# node_captorIR.net
KiCad netlist of a schematic drawn in EAGLE
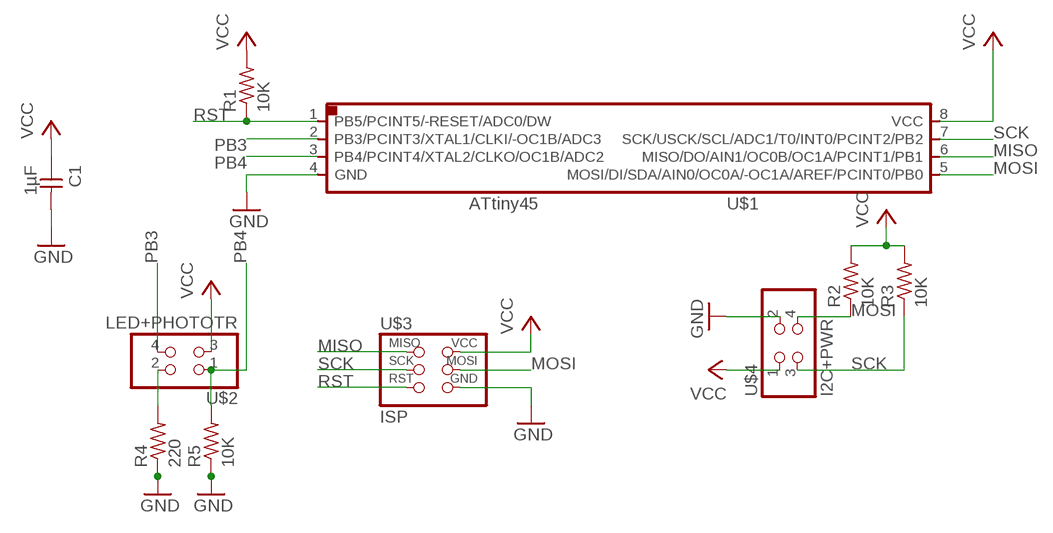
[diagram p0: schematic, sheet 1]

(export (version "E")
  (design (tool "Eeschema 10.0.6"))
  (components
    (comp (ref "C1")
      (value "1µF")
      (footprint "eagle-import:C1206FAB")
      (libsource (lib "eagle-import") (part "CAP-UNPOLARIZEDFAB"))
    )
    (comp (ref "R1")
      (value "10K")
      (footprint "eagle-import:R1206FAB")
      (libsource (lib "eagle-import") (part "RES-US1206FAB"))
    )
    (comp (ref "R2")
      (value "10K")
      (footprint "eagle-import:R1206FAB")
      (libsource (lib "eagle-import") (part "RES-US1206FAB"))
    )
    (comp (ref "R3")
      (value "10K")
      (footprint "eagle-import:R1206FAB")
      (libsource (lib "eagle-import") (part "RES-US1206FAB"))
    )
    (comp (ref "R4")
      (value "220")
      (footprint "eagle-import:R1206FAB")
      (libsource (lib "eagle-import") (part "RES-US1206FAB"))
    )
    (comp (ref "R5")
      (value "10K")
      (footprint "eagle-import:R1206FAB")
      (libsource (lib "eagle-import") (part "RES-US1206FAB"))
    )
    (comp (ref "U$1")
      (value "ATTINY45SI")
      (footprint "eagle-import:SOIC8")
      (libsource (lib "eagle-import") (part "ATTINY45SI"))
    )
    (comp (ref "U$2")
      (value "LED+PHOTOTR")
      (footprint "eagle-import:2X02SMD")
      (libsource (lib "eagle-import") (part "PINHD-2X2-SMD"))
    )
    (comp (ref "U$3")
      (value "ISP")
      (footprint "eagle-import:2X03SMD")
      (libsource (lib "eagle-import") (part "AVRISPSMD"))
    )
    (comp (ref "U$4")
      (value "I2C+PWR")
      (footprint "eagle-import:2X02SMD")
      (libsource (lib "eagle-import") (part "PINHD-2X2-SMD"))
    )
  )
  (nets
    (net (code "1") (name "/MISO") (class "Default")
      (node (ref "U$1") (pin "6") (pinfunction "MISO/DO/AIN1/OC0B/OC1A/PCINT1/PB1_6") (pintype "bidirectional"))
      (node (ref "U$3") (pin "1") (pinfunction "MISO_1") (pintype "passive"))
    )
    (net (code "2") (name "/MOSI") (class "Default")
      (node (ref "R2") (pin "1") (pinfunction "1_1") (pintype "passive"))
      (node (ref "U$1") (pin "5") (pinfunction "MOSI/DI/SDA/AIN0/OC0A/-OC1A/AREF/PCINT0/PB0_5") (pintype "bidirectional"))
      (node (ref "U$3") (pin "4") (pinfunction "MOSI_4") (pintype "passive"))
      (node (ref "U$4") (pin "4") (pinfunction "4_4") (pintype "passive"))
    )
    (net (code "3") (name "/PB3") (class "Default")
      (node (ref "U$1") (pin "2") (pinfunction "PB3/PCINT3/XTAL1/CLKI/-OC1B/ADC3_2") (pintype "bidirectional"))
      (node (ref "U$2") (pin "4") (pinfunction "4_4") (pintype "passive"))
    )
    (net (code "4") (name "/PB4") (class "Default")
      (node (ref "R5") (pin "2") (pinfunction "2_2") (pintype "passive"))
      (node (ref "U$1") (pin "3") (pinfunction "PB4/PCINT4/XTAL2/CLKO/OC1B/ADC2_3") (pintype "bidirectional"))
      (node (ref "U$2") (pin "1") (pinfunction "1_1") (pintype "passive"))
    )
    (net (code "5") (name "/RST") (class "Default")
      (node (ref "R1") (pin "1") (pinfunction "1_1") (pintype "passive"))
      (node (ref "U$1") (pin "1") (pinfunction "PB5/PCINT5/-RESET/ADC0/DW_1") (pintype "bidirectional"))
      (node (ref "U$3") (pin "5") (pinfunction "RST_5") (pintype "passive"))
    )
    (net (code "6") (name "/SCK") (class "Default")
      (node (ref "R3") (pin "1") (pinfunction "1_1") (pintype "passive"))
      (node (ref "U$1") (pin "7") (pinfunction "SCK/USCK/SCL/ADC1/T0/INT0/PCINT2/PB2_7") (pintype "bidirectional"))
      (node (ref "U$3") (pin "3") (pinfunction "SCK_3") (pintype "passive"))
      (node (ref "U$4") (pin "3") (pinfunction "3_3") (pintype "passive"))
    )
    (net (code "7") (name "GND") (class "Default")
      (node (ref "C1") (pin "2") (pinfunction "2_2") (pintype "passive"))
      (node (ref "R4") (pin "1") (pinfunction "1_1") (pintype "passive"))
      (node (ref "R5") (pin "1") (pinfunction "1_1") (pintype "passive"))
      (node (ref "U$1") (pin "4") (pinfunction "GND_4") (pintype "bidirectional"))
      (node (ref "U$3") (pin "6") (pinfunction "GND_6") (pintype "passive"))
      (node (ref "U$4") (pin "2") (pinfunction "2_2") (pintype "passive"))
    )
    (net (code "8") (name "Net-(R4-Pad2)") (class "Default")
      (node (ref "R4") (pin "2") (pinfunction "2_2") (pintype "passive"))
      (node (ref "U$2") (pin "2") (pinfunction "2_2") (pintype "passive"))
    )
    (net (code "9") (name "VCC") (class "Default")
      (node (ref "C1") (pin "1") (pinfunction "1_1") (pintype "passive"))
      (node (ref "R1") (pin "2") (pinfunction "2_2") (pintype "passive"))
      (node (ref "R2") (pin "2") (pinfunction "2_2") (pintype "passive"))
      (node (ref "R3") (pin "2") (pinfunction "2_2") (pintype "passive"))
      (node (ref "U$1") (pin "8") (pinfunction "VCC_8") (pintype "bidirectional"))
      (node (ref "U$2") (pin "3") (pinfunction "3_3") (pintype "passive"))
      (node (ref "U$3") (pin "2") (pinfunction "VCC_2") (pintype "passive"))
      (node (ref "U$4") (pin "1") (pinfunction "1_1") (pintype "passive"))
    )
  )
)
